# Relay_outputs1.net
KiCad netlist of a schematic drawn in EAGLE
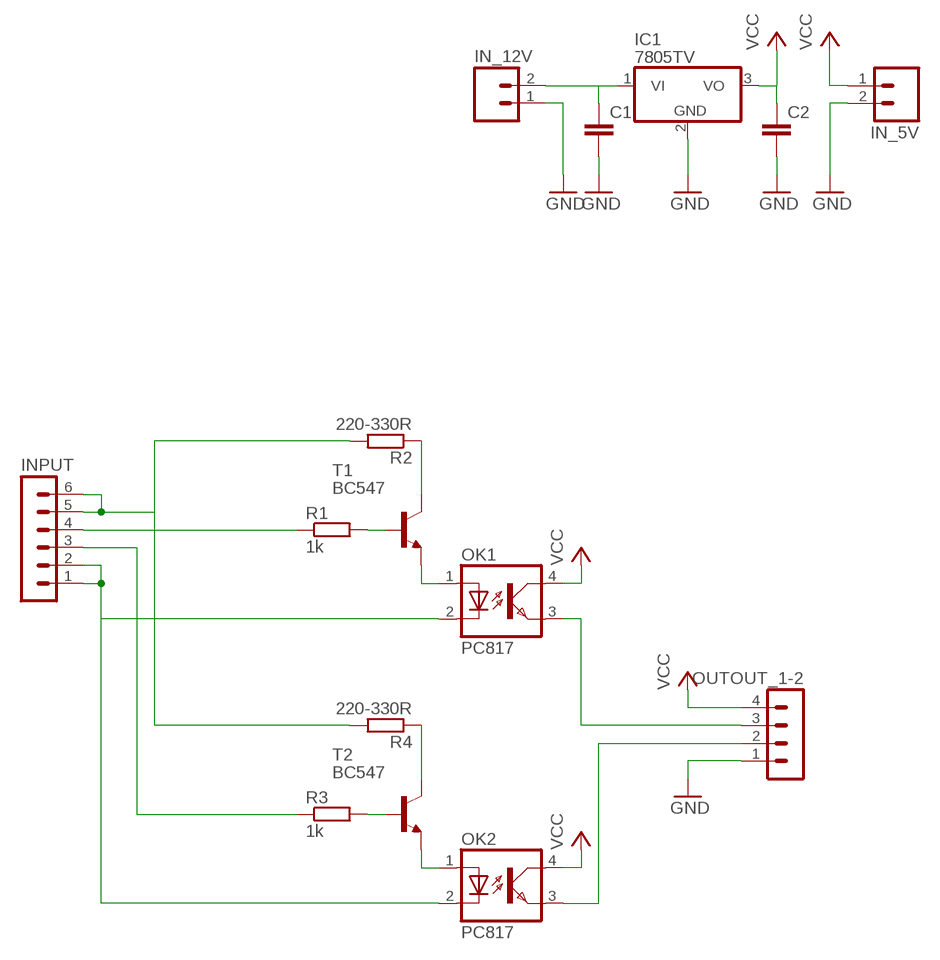
[diagram p0: schematic, sheet 1]

(export (version "E")
  (design (tool "Eeschema 10.0.6"))
  (components
    (comp (ref "C1")
      (value "C-EU050-024X044")
      (footprint "eagle-import:C050-024X044")
      (libsource (lib "eagle-import") (part "C-EU050-024X044"))
    )
    (comp (ref "C2")
      (value "C-EU050-024X044")
      (footprint "eagle-import:C050-024X044")
      (libsource (lib "eagle-import") (part "C-EU050-024X044"))
    )
    (comp (ref "IC1")
      (value "7805TV")
      (footprint "eagle-import:TO220V")
      (libsource (lib "eagle-import") (part "78TV05"))
    )
    (comp (ref "INPUT")
      (value "MA06-1")
      (footprint "eagle-import:MA06-1")
      (libsource (lib "eagle-import") (part "MA06-1"))
    )
    (comp (ref "IN_5V")
      (value "MA02")
      (footprint "eagle-import:02PA")
      (libsource (lib "eagle-import") (part "MA02"))
    )
    (comp (ref "IN_12V")
      (value "MA02")
      (footprint "eagle-import:02PA")
      (libsource (lib "eagle-import") (part "MA02"))
    )
    (comp (ref "OK1")
      (value "PC817")
      (footprint "eagle-import:DIL04")
      (libsource (lib "eagle-import") (part "PC817"))
    )
    (comp (ref "OK2")
      (value "PC817")
      (footprint "eagle-import:DIL04")
      (libsource (lib "eagle-import") (part "PC817"))
    )
    (comp (ref "OUTOUT_1-2")
      (value "MA04-1")
      (footprint "eagle-import:MA04-1")
      (libsource (lib "eagle-import") (part "MA04-1"))
    )
    (comp (ref "R1")
      (value "1k")
      (footprint "eagle-import:0207_10")
      (libsource (lib "eagle-import") (part "R-EU_0207/10"))
    )
    (comp (ref "R2")
      (value "220-330R")
      (footprint "eagle-import:0207_10")
      (libsource (lib "eagle-import") (part "R-EU_0207/10"))
    )
    (comp (ref "R3")
      (value "1k")
      (footprint "eagle-import:0207_10")
      (libsource (lib "eagle-import") (part "R-EU_0207/10"))
    )
    (comp (ref "R4")
      (value "220-330R")
      (footprint "eagle-import:0207_10")
      (libsource (lib "eagle-import") (part "R-EU_0207/10"))
    )
    (comp (ref "T1")
      (value "BC547")
      (footprint "eagle-import:TO92")
      (libsource (lib "eagle-import") (part "BC547"))
    )
    (comp (ref "T2")
      (value "BC547")
      (footprint "eagle-import:TO92")
      (libsource (lib "eagle-import") (part "BC547"))
    )
  )
  (nets
    (net (code "1") (name "GND") (class "Default")
      (node (ref "C1") (pin "2") (pinfunction "2_2") (pintype "passive"))
      (node (ref "C2") (pin "2") (pinfunction "2_2") (pintype "passive"))
      (node (ref "IC1") (pin "2") (pinfunction "GND_2") (pintype "passive"))
      (node (ref "IN_12V") (pin "1") (pinfunction "1_1") (pintype "passive"))
      (node (ref "IN_5V") (pin "2") (pinfunction "2_2") (pintype "passive"))
      (node (ref "OUTOUT_1-2") (pin "1") (pinfunction "1_1") (pintype "passive"))
    )
    (net (code "2") (name "Net-(IC1-VI)") (class "Default")
      (node (ref "C1") (pin "1") (pinfunction "1_1") (pintype "passive"))
      (node (ref "IC1") (pin "1") (pinfunction "VI_1") (pintype "input"))
      (node (ref "IN_12V") (pin "2") (pinfunction "2_2") (pintype "passive"))
    )
    (net (code "3") (name "Net-(INPUT-Pad3)") (class "Default")
      (node (ref "INPUT") (pin "3") (pinfunction "3_3") (pintype "passive"))
      (node (ref "R3") (pin "1") (pinfunction "1_1") (pintype "passive"))
    )
    (net (code "4") (name "Net-(INPUT-Pad4)") (class "Default")
      (node (ref "INPUT") (pin "4") (pinfunction "4_4") (pintype "passive"))
      (node (ref "R1") (pin "1") (pinfunction "1_1") (pintype "passive"))
    )
    (net (code "5") (name "Net-(INPUT-Pad5)") (class "Default")
      (node (ref "INPUT") (pin "5") (pinfunction "5_5") (pintype "passive"))
      (node (ref "INPUT") (pin "6") (pinfunction "6_6") (pintype "passive"))
      (node (ref "R2") (pin "2") (pinfunction "2_2") (pintype "passive"))
      (node (ref "R4") (pin "2") (pinfunction "2_2") (pintype "passive"))
    )
    (net (code "6") (name "Net-(OK1-A)") (class "Default")
      (node (ref "OK1") (pin "1") (pinfunction "A_1") (pintype "passive"))
      (node (ref "T1") (pin "1") (pinfunction "E_1") (pintype "passive"))
    )
    (net (code "7") (name "Net-(OK1-C)") (class "Default")
      (node (ref "INPUT") (pin "1") (pinfunction "1_1") (pintype "passive"))
      (node (ref "INPUT") (pin "2") (pinfunction "2_2") (pintype "passive"))
      (node (ref "OK1") (pin "2") (pinfunction "C_2") (pintype "passive"))
      (node (ref "OK2") (pin "2") (pinfunction "C_2") (pintype "passive"))
    )
    (net (code "8") (name "Net-(OK1-EMIT)") (class "Default")
      (node (ref "OK1") (pin "3") (pinfunction "EMIT_3") (pintype "passive"))
      (node (ref "OUTOUT_1-2") (pin "3") (pinfunction "3_3") (pintype "passive"))
    )
    (net (code "9") (name "Net-(OK2-A)") (class "Default")
      (node (ref "OK2") (pin "1") (pinfunction "A_1") (pintype "passive"))
      (node (ref "T2") (pin "1") (pinfunction "E_1") (pintype "passive"))
    )
    (net (code "10") (name "Net-(OK2-EMIT)") (class "Default")
      (node (ref "OK2") (pin "3") (pinfunction "EMIT_3") (pintype "passive"))
      (node (ref "OUTOUT_1-2") (pin "2") (pinfunction "2_2") (pintype "passive"))
    )
    (net (code "11") (name "Net-(T1-B)") (class "Default")
      (node (ref "R1") (pin "2") (pinfunction "2_2") (pintype "passive"))
      (node (ref "T1") (pin "2") (pinfunction "B_2") (pintype "passive"))
    )
    (net (code "12") (name "Net-(T1-C)") (class "Default")
      (node (ref "R2") (pin "1") (pinfunction "1_1") (pintype "passive"))
      (node (ref "T1") (pin "3") (pinfunction "C_3") (pintype "passive"))
    )
    (net (code "13") (name "Net-(T2-B)") (class "Default")
      (node (ref "R3") (pin "2") (pinfunction "2_2") (pintype "passive"))
      (node (ref "T2") (pin "2") (pinfunction "B_2") (pintype "passive"))
    )
    (net (code "14") (name "Net-(T2-C)") (class "Default")
      (node (ref "R4") (pin "1") (pinfunction "1_1") (pintype "passive"))
      (node (ref "T2") (pin "3") (pinfunction "C_3") (pintype "passive"))
    )
    (net (code "15") (name "VCC") (class "Default")
      (node (ref "C2") (pin "1") (pinfunction "1_1") (pintype "passive"))
      (node (ref "IC1") (pin "3") (pinfunction "VO_3") (pintype "passive"))
      (node (ref "IN_5V") (pin "1") (pinfunction "1_1") (pintype "passive"))
      (node (ref "OK1") (pin "4") (pinfunction "COL_4") (pintype "passive"))
      (node (ref "OK2") (pin "4") (pinfunction "COL_4") (pintype "passive"))
      (node (ref "OUTOUT_1-2") (pin "4") (pinfunction "4_4") (pintype "passive"))
    )
  )
)
